# drvoutput2.net
KiCad netlist of a schematic drawn in Altium Designer
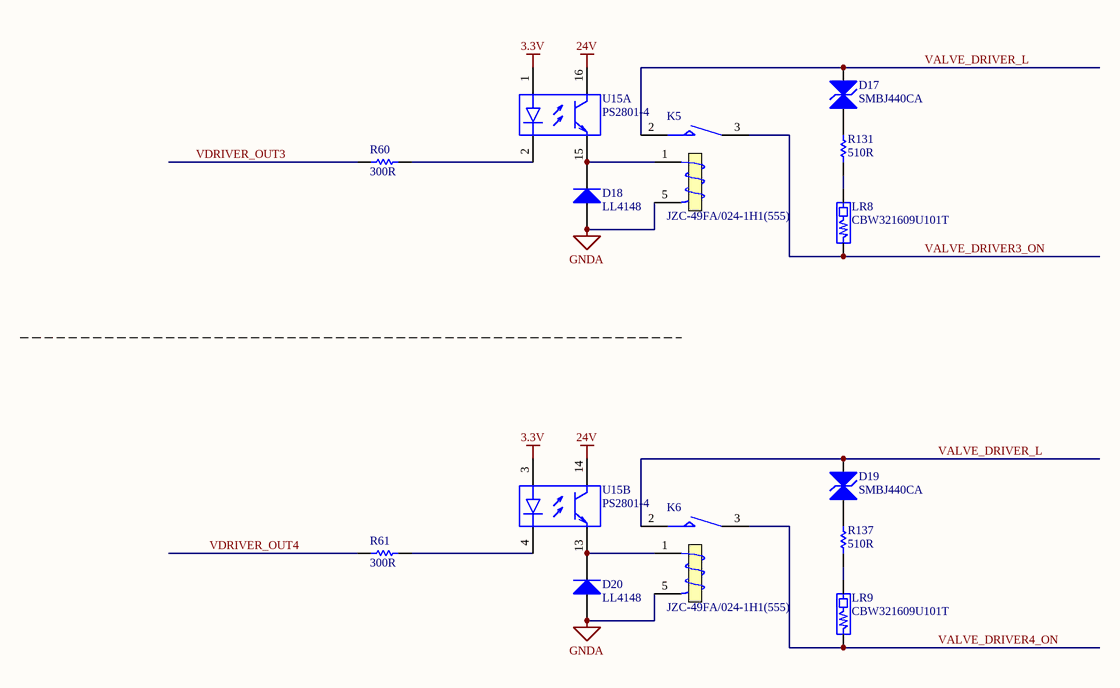
[diagram p0: drvoutput2.SchDoc]

(export (version "E")
  (design (tool "Eeschema 10.0.6"))
  (components
    (comp (ref "D17")
      (value "SMBJ440CA")
      (footprint "SMB")
      (description "Bi-dir TVS Diode")
      (fields (field (name "PUBLISHER") "Altium Limited"))
      (libsource (lib "UserLib") (part "Bi-dir TVS Diode"))
    )
    (comp (ref "D18")
      (value "LL4148")
      (footprint "CD2012-0805")
      (description "1 Amp General Purpose Rectifier")
      (fields (field (name "PUBLISHER") "Altium Limited"))
      (libsource (lib "Miscellaneous Devices") (part "Diode 1N4007"))
    )
    (comp (ref "D19")
      (value "SMBJ440CA")
      (footprint "SMB")
      (description "Bi-dir TVS Diode")
      (fields (field (name "PUBLISHER") "Altium Limited"))
      (libsource (lib "UserLib") (part "Bi-dir TVS Diode"))
    )
    (comp (ref "D20")
      (value "LL4148")
      (footprint "CD2012-0805")
      (description "1 Amp General Purpose Rectifier")
      (fields (field (name "PUBLISHER") "Altium Limited"))
      (libsource (lib "Miscellaneous Devices") (part "Diode 1N4007"))
    )
    (comp (ref "K5")
      (value "JZC-49FA/024-1H1(555)")
      (footprint "JZC-49FA")
      (description "Intermediate  Power  Relay")
      (fields (field (name "PUBLISHER") "Altium Limited"))
      (libsource (lib "UserSchDev") (part "JZC-49FA"))
    )
    (comp (ref "K6")
      (value "JZC-49FA/024-1H1(555)")
      (footprint "JZC-49FA")
      (description "Intermediate  Power  Relay")
      (fields (field (name "PUBLISHER") "Altium Limited"))
      (libsource (lib "UserSchDev") (part "JZC-49FA"))
    )
    (comp (ref "LR8")
      (value "CBW321609U101T")
      (footprint "INDC3216M")
      (description "EMI FILTERS,DC Resistance max.0.05~1.5 ohms,10 ~ 1000 ohms at 100MHz  Frequency")
      (libsource (lib "UserLib") (part "BLM10/11/21/31/41"))
    )
    (comp (ref "LR9")
      (value "CBW321609U101T")
      (footprint "INDC3216M")
      (description "EMI FILTERS,DC Resistance max.0.05~1.5 ohms,10 ~ 1000 ohms at 100MHz  Frequency")
      (libsource (lib "UserLib") (part "BLM10/11/21/31/41"))
    )
    (comp (ref "R60")
      (value "300R")
      (footprint "RESC2012M")
      (description "Resistor")
      (fields (field (name "PUBLISHER") "Altium Limited"))
      (libsource (lib "Miscellaneous Devices") (part "Res1"))
    )
    (comp (ref "R61")
      (value "300R")
      (footprint "RESC2012M")
      (description "Resistor")
      (fields (field (name "PUBLISHER") "Altium Limited"))
      (libsource (lib "Miscellaneous Devices") (part "Res1"))
    )
    (comp (ref "R131")
      (value "510R")
      (footprint "RESC3216M")
      (description "Metal film Resistor")
      (fields (field (name "PUBLISHER") "Altium Limited"))
      (libsource (lib "Miscellaneous Devices") (part "Res1"))
    )
    (comp (ref "R137")
      (value "510R")
      (footprint "RESC3216M")
      (description "Metal film Resistor")
      (fields (field (name "PUBLISHER") "Altium Limited"))
      (libsource (lib "Miscellaneous Devices") (part "Res1"))
    )
    (comp (ref "U15")
      (value "PS2801-4")
      (footprint "SOIC16_N")
      (fields (field (name "PUBLISHER") "Altium Limited"))
      (libsource (lib "UserSchDev") (part "PS2801-4"))
    )
  )
  (nets
    (net (code "1") (name "/VALVE_DRIVER3_ON") (class "Default")
      (node (ref "K5") (pin "3") (pinfunction "NO_3") (pintype "passive"))
      (node (ref "LR8") (pin "1") (pinfunction "1_1") (pintype "passive"))
    )
    (net (code "2") (name "/VALVE_DRIVER4_ON") (class "Default")
      (node (ref "K6") (pin "3") (pinfunction "NO_3") (pintype "passive"))
      (node (ref "LR9") (pin "1") (pinfunction "1_1") (pintype "passive"))
    )
    (net (code "3") (name "/VALVE_DRIVER_L") (class "Default")
      (node (ref "D17") (pin "2") (pinfunction "K_2") (pintype "passive"))
      (node (ref "D19") (pin "2") (pinfunction "K_2") (pintype "passive"))
      (node (ref "K5") (pin "2") (pinfunction "COM_2") (pintype "passive"))
      (node (ref "K6") (pin "2") (pinfunction "COM_2") (pintype "passive"))
    )
    (net (code "4") (name "/VDRIVER_OUT3") (class "Default")
      (node (ref "R60") (pin "1") (pinfunction "1_1") (pintype "passive"))
    )
    (net (code "5") (name "/VDRIVER_OUT4") (class "Default")
      (node (ref "R61") (pin "1") (pinfunction "1_1") (pintype "passive"))
    )
    (net (code "6") (name "3.3V") (class "Default")
      (node (ref "U15") (pin "1") (pinfunction "+_1") (pintype "passive"))
      (node (ref "U15") (pin "3") (pinfunction "+_3") (pintype "passive"))
    )
    (net (code "7") (name "24V") (class "Default")
      (node (ref "U15") (pin "14") (pinfunction "C_14") (pintype "passive"))
      (node (ref "U15") (pin "16") (pinfunction "C_16") (pintype "passive"))
    )
    (net (code "8") (name "GNDA") (class "Default")
      (node (ref "D18") (pin "1") (pinfunction "A_1") (pintype "passive"))
      (node (ref "D20") (pin "1") (pinfunction "A_1") (pintype "passive"))
      (node (ref "K5") (pin "5") (pinfunction "T2_5") (pintype "passive"))
      (node (ref "K6") (pin "5") (pinfunction "T2_5") (pintype "passive"))
    )
    (net (code "9") (name "Net-(D17-A)") (class "Default")
      (node (ref "D17") (pin "1") (pinfunction "A_1") (pintype "passive"))
      (node (ref "R131") (pin "2") (pinfunction "2_2") (pintype "passive"))
    )
    (net (code "10") (name "Net-(D18-K)") (class "Default")
      (node (ref "D18") (pin "2") (pinfunction "K_2") (pintype "passive"))
      (node (ref "K5") (pin "1") (pinfunction "1_1") (pintype "passive"))
      (node (ref "U15") (pin "15") (pinfunction "E_15") (pintype "passive"))
    )
    (net (code "11") (name "Net-(D19-A)") (class "Default")
      (node (ref "D19") (pin "1") (pinfunction "A_1") (pintype "passive"))
      (node (ref "R137") (pin "2") (pinfunction "2_2") (pintype "passive"))
    )
    (net (code "12") (name "Net-(D20-K)") (class "Default")
      (node (ref "D20") (pin "2") (pinfunction "K_2") (pintype "passive"))
      (node (ref "K6") (pin "1") (pinfunction "1_1") (pintype "passive"))
      (node (ref "U15") (pin "13") (pinfunction "E_13") (pintype "passive"))
    )
    (net (code "13") (name "Net-(LR8-Pad2)") (class "Default")
      (node (ref "LR8") (pin "2") (pinfunction "2_2") (pintype "passive"))
      (node (ref "R131") (pin "1") (pinfunction "1_1") (pintype "passive"))
    )
    (net (code "14") (name "Net-(LR9-Pad2)") (class "Default")
      (node (ref "LR9") (pin "2") (pinfunction "2_2") (pintype "passive"))
      (node (ref "R137") (pin "1") (pinfunction "1_1") (pintype "passive"))
    )
    (net (code "15") (name "Net-(U15A--)") (class "Default")
      (node (ref "R60") (pin "2") (pinfunction "2_2") (pintype "passive"))
      (node (ref "U15") (pin "2") (pinfunction "-_2") (pintype "passive"))
    )
    (net (code "16") (name "Net-(U15B--)") (class "Default")
      (node (ref "R61") (pin "2") (pinfunction "2_2") (pintype "passive"))
      (node (ref "U15") (pin "4") (pinfunction "-_4") (pintype "passive"))
    )
  )
)
